# XmasTreeCard.net
KiCad netlist of a schematic drawn in EAGLE
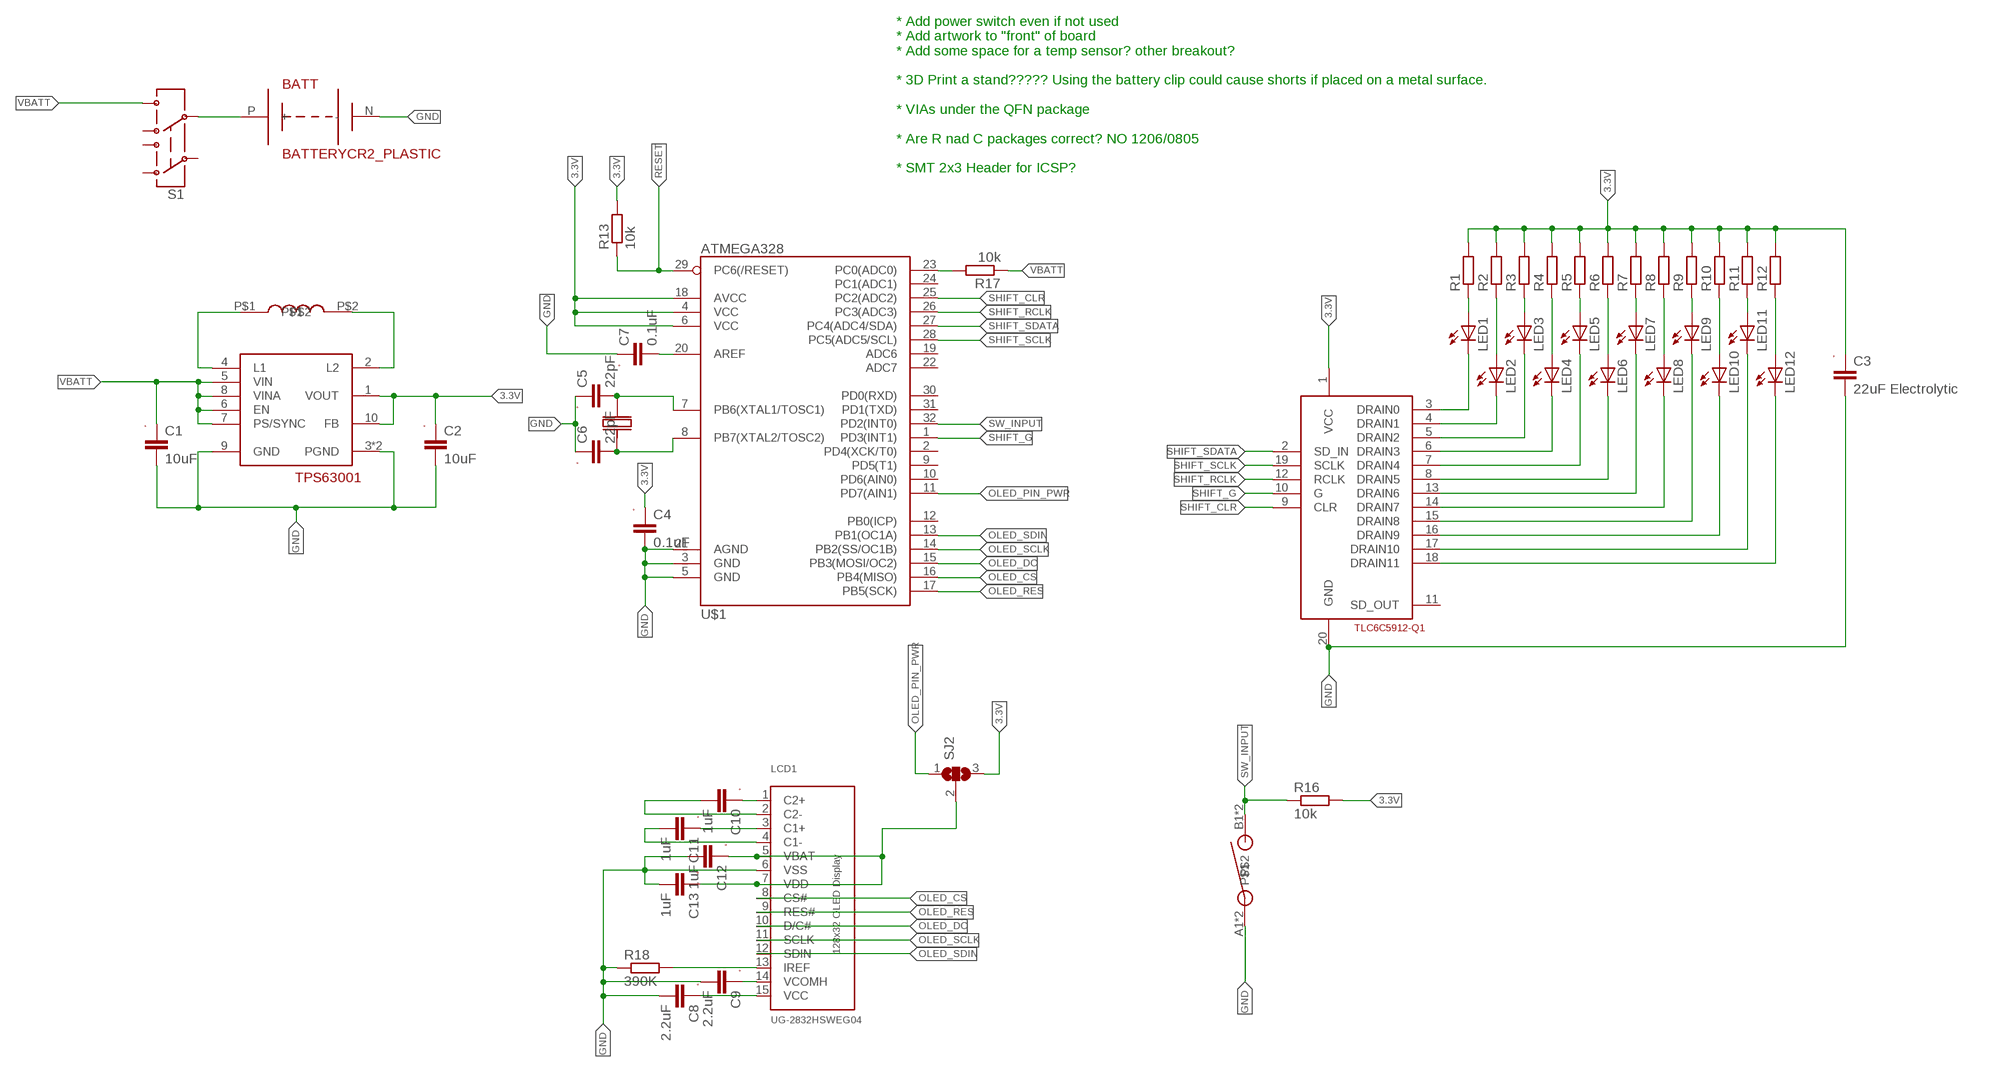
[diagram p0: schematic, sheet 1]

(export (version "E")
  (design (tool "Eeschema 10.0.6"))
  (components
    (comp (ref "BATT")
      (value "BATTERYCR2_PLASTIC")
      (footprint "eagle-import:BATT_SMD_CR2_PLASTIC")
      (libsource (lib "eagle-import") (part "BATTERYCR2_PLASTIC"))
    )
    (comp (ref "C1")
      (value "10uF")
      (footprint "eagle-import:C1206")
      (libsource (lib "eagle-import") (part "C-EUC1206"))
    )
    (comp (ref "C2")
      (value "10uF")
      (footprint "eagle-import:C1206")
      (libsource (lib "eagle-import") (part "C-EUC1206"))
    )
    (comp (ref "C3")
      (value "22uF Electrolytic")
      (footprint "eagle-import:CAP_2012-15")
      (libsource (lib "eagle-import") (part "C-EUAVX_TAJ_P"))
    )
    (comp (ref "C4")
      (value "0.1uF")
      (footprint "eagle-import:C0805K")
      (libsource (lib "eagle-import") (part "C-EUC0805K"))
    )
    (comp (ref "C5")
      (value "22pF")
      (footprint "eagle-import:C0805K")
      (libsource (lib "eagle-import") (part "C-EUC0805K"))
    )
    (comp (ref "C6")
      (value "22pF")
      (footprint "eagle-import:C0805K")
      (libsource (lib "eagle-import") (part "C-EUC0805K"))
    )
    (comp (ref "C7")
      (value "0.1uF")
      (footprint "eagle-import:C0805K")
      (libsource (lib "eagle-import") (part "C-EUC0805K"))
    )
    (comp (ref "C8")
      (value "2.2uF")
      (footprint "eagle-import:C1206")
      (libsource (lib "eagle-import") (part "C-EUC1206"))
    )
    (comp (ref "C9")
      (value "2.2uF")
      (footprint "eagle-import:C1206")
      (libsource (lib "eagle-import") (part "C-EUC1206"))
    )
    (comp (ref "C10")
      (value "1uF")
      (footprint "eagle-import:C1206")
      (libsource (lib "eagle-import") (part "C-EUC1206"))
    )
    (comp (ref "C11")
      (value "1uF")
      (footprint "eagle-import:C1206")
      (libsource (lib "eagle-import") (part "C-EUC1206"))
    )
    (comp (ref "C12")
      (value "1uF")
      (footprint "eagle-import:C1206")
      (libsource (lib "eagle-import") (part "C-EUC1206"))
    )
    (comp (ref "C13")
      (value "1uF")
      (footprint "eagle-import:C1206")
      (libsource (lib "eagle-import") (part "C-EUC1206"))
    )
    (comp (ref "LCD1")
      (value "UG-2832HSWEG04")
      (footprint "eagle-import:UG-283HSWEG04_FOLDAROUND")
      (libsource (lib "eagle-import") (part "OLED_UG-2832HSWEG04FOLDAROUND"))
    )
    (comp (ref "LED1")
      (value "LEDCHIPLED_0805")
      (footprint "eagle-import:CHIPLED_0805")
      (libsource (lib "eagle-import") (part "LEDCHIPLED_0805"))
    )
    (comp (ref "LED2")
      (value "LEDCHIPLED_0805")
      (footprint "eagle-import:CHIPLED_0805")
      (libsource (lib "eagle-import") (part "LEDCHIPLED_0805"))
    )
    (comp (ref "LED3")
      (value "LEDCHIPLED_0805")
      (footprint "eagle-import:CHIPLED_0805")
      (libsource (lib "eagle-import") (part "LEDCHIPLED_0805"))
    )
    (comp (ref "LED4")
      (value "LEDCHIPLED_0805")
      (footprint "eagle-import:CHIPLED_0805")
      (libsource (lib "eagle-import") (part "LEDCHIPLED_0805"))
    )
    (comp (ref "LED5")
      (value "LEDCHIPLED_0805")
      (footprint "eagle-import:CHIPLED_0805")
      (libsource (lib "eagle-import") (part "LEDCHIPLED_0805"))
    )
    (comp (ref "LED6")
      (value "LEDCHIPLED_0805")
      (footprint "eagle-import:CHIPLED_0805")
      (libsource (lib "eagle-import") (part "LEDCHIPLED_0805"))
    )
    (comp (ref "LED7")
      (value "LEDCHIPLED_0805")
      (footprint "eagle-import:CHIPLED_0805")
      (libsource (lib "eagle-import") (part "LEDCHIPLED_0805"))
    )
    (comp (ref "LED8")
      (value "LEDCHIPLED_0805")
      (footprint "eagle-import:CHIPLED_0805")
      (libsource (lib "eagle-import") (part "LEDCHIPLED_0805"))
    )
    (comp (ref "LED9")
      (value "LEDCHIPLED_0805")
      (footprint "eagle-import:CHIPLED_0805")
      (libsource (lib "eagle-import") (part "LEDCHIPLED_0805"))
    )
    (comp (ref "LED10")
      (value "LEDCHIPLED_0805")
      (footprint "eagle-import:CHIPLED_0805")
      (libsource (lib "eagle-import") (part "LEDCHIPLED_0805"))
    )
    (comp (ref "LED11")
      (value "LEDCHIPLED_0805")
      (footprint "eagle-import:CHIPLED_0805")
      (libsource (lib "eagle-import") (part "LEDCHIPLED_0805"))
    )
    (comp (ref "LED12")
      (value "LEDCHIPLED_0805")
      (footprint "eagle-import:CHIPLED_0805")
      (libsource (lib "eagle-import") (part "LEDCHIPLED_0805"))
    )
    (comp (ref "R1")
      (value "R-EUR0805")
      (footprint "eagle-import:R0805")
      (libsource (lib "eagle-import") (part "R-EUR0805"))
    )
    (comp (ref "R2")
      (value "R-EUR0805")
      (footprint "eagle-import:R0805")
      (libsource (lib "eagle-import") (part "R-EUR0805"))
    )
    (comp (ref "R3")
      (value "R-EUR0805")
      (footprint "eagle-import:R0805")
      (libsource (lib "eagle-import") (part "R-EUR0805"))
    )
    (comp (ref "R4")
      (value "R-EUR0805")
      (footprint "eagle-import:R0805")
      (libsource (lib "eagle-import") (part "R-EUR0805"))
    )
    (comp (ref "R5")
      (value "R-EUR0805")
      (footprint "eagle-import:R0805")
      (libsource (lib "eagle-import") (part "R-EUR0805"))
    )
    (comp (ref "R6")
      (value "R-EUR0805")
      (footprint "eagle-import:R0805")
      (libsource (lib "eagle-import") (part "R-EUR0805"))
    )
    (comp (ref "R7")
      (value "R-EUR0805")
      (footprint "eagle-import:R0805")
      (libsource (lib "eagle-import") (part "R-EUR0805"))
    )
    (comp (ref "R8")
      (value "R-EUR0805")
      (footprint "eagle-import:R0805")
      (libsource (lib "eagle-import") (part "R-EUR0805"))
    )
    (comp (ref "R9")
      (value "R-EUR0805")
      (footprint "eagle-import:R0805")
      (libsource (lib "eagle-import") (part "R-EUR0805"))
    )
    (comp (ref "R10")
      (value "R-EUR0805")
      (footprint "eagle-import:R0805")
      (libsource (lib "eagle-import") (part "R-EUR0805"))
    )
    (comp (ref "R11")
      (value "R-EUR0805")
      (footprint "eagle-import:R0805")
      (libsource (lib "eagle-import") (part "R-EUR0805"))
    )
    (comp (ref "R12")
      (value "R-EUR0805")
      (footprint "eagle-import:R0805")
      (libsource (lib "eagle-import") (part "R-EUR0805"))
    )
    (comp (ref "R13")
      (value "10k")
      (footprint "eagle-import:R0805")
      (libsource (lib "eagle-import") (part "R-EUR0805"))
    )
    (comp (ref "R16")
      (value "10k")
      (footprint "eagle-import:R0805")
      (libsource (lib "eagle-import") (part "R-EUR0805"))
    )
    (comp (ref "R17")
      (value "10k")
      (footprint "eagle-import:R0805")
      (libsource (lib "eagle-import") (part "R-EUR0805"))
    )
    (comp (ref "R18")
      (value "390K")
      (footprint "eagle-import:R0805")
      (libsource (lib "eagle-import") (part "R-EUR0805"))
    )
    (comp (ref "S1")
      (value "SWITCH-DPDTMMS228")
      (footprint "eagle-import:MMS_228_T")
      (libsource (lib "eagle-import") (part "SWITCH-DPDTMMS228"))
    )
    (comp (ref "SJ2")
      (value "SJ2W")
      (footprint "eagle-import:SJ_2")
      (libsource (lib "eagle-import") (part "SJ2W"))
    )
    (comp (ref "SW1")
      (value "SWITCH_SPST6X6TACTILE")
      (footprint "eagle-import:SWITCH_SPST_6X6_TACTILE")
      (libsource (lib "eagle-import") (part "SWITCH_SPST6X6TACTILE"))
    )
    (comp (ref "U$1")
      (value "ATMEGA328")
      (footprint "eagle-import:TQFP32-08")
      (libsource (lib "eagle-import") (part "ATMEGA328_SMT"))
    )
    (comp (ref "U$2")
      (value "COILCRAFT_LPS4012")
      (footprint "eagle-import:COILCRAFT_LPS4012")
      (libsource (lib "eagle-import") (part "COILCRAFT_LPS4012"))
    )
    (comp (ref "U$3")
      (value "TPS63001DRC")
      (footprint "eagle-import:QFN10_3X3MM")
      (libsource (lib "eagle-import") (part "TPS63001DRC"))
    )
    (comp (ref "U$4")
      (value "TLC6C5912-Q1")
      (footprint "eagle-import:TSSOP-20")
      (libsource (lib "eagle-import") (part "TLC6C5912-Q1"))
    )
    (comp (ref "U$5")
      (value "CRYSTAL_ABM03")
      (footprint "eagle-import:ABM_CRYSTAL")
      (libsource (lib "eagle-import") (part "CRYSTAL_ABM03"))
    )
  )
  (nets
    (net (code "1") (name "3.3V") (class "Default")
      (node (ref "C2") (pin "1") (pinfunction "1_1") (pintype "passive"))
      (node (ref "C3") (pin "P") (pinfunction "1_P") (pintype "passive"))
      (node (ref "C4") (pin "1") (pinfunction "1_1") (pintype "passive"))
      (node (ref "R1") (pin "2") (pinfunction "2_2") (pintype "passive"))
      (node (ref "R10") (pin "2") (pinfunction "2_2") (pintype "passive"))
      (node (ref "R11") (pin "2") (pinfunction "2_2") (pintype "passive"))
      (node (ref "R12") (pin "2") (pinfunction "2_2") (pintype "passive"))
      (node (ref "R13") (pin "2") (pinfunction "2_2") (pintype "passive"))
      (node (ref "R16") (pin "2") (pinfunction "2_2") (pintype "passive"))
      (node (ref "R2") (pin "2") (pinfunction "2_2") (pintype "passive"))
      (node (ref "R3") (pin "2") (pinfunction "2_2") (pintype "passive"))
      (node (ref "R4") (pin "2") (pinfunction "2_2") (pintype "passive"))
      (node (ref "R5") (pin "2") (pinfunction "2_2") (pintype "passive"))
      (node (ref "R6") (pin "2") (pinfunction "2_2") (pintype "passive"))
      (node (ref "R7") (pin "2") (pinfunction "2_2") (pintype "passive"))
      (node (ref "R8") (pin "2") (pinfunction "2_2") (pintype "passive"))
      (node (ref "R9") (pin "2") (pinfunction "2_2") (pintype "passive"))
      (node (ref "SJ2") (pin "3") (pinfunction "3_3") (pintype "passive"))
      (node (ref "U$1") (pin "18") (pinfunction "AVCC_18") (pintype "bidirectional"))
      (node (ref "U$1") (pin "4") (pinfunction "VCC_4") (pintype "bidirectional"))
      (node (ref "U$1") (pin "6") (pinfunction "VCC_6") (pintype "bidirectional"))
      (node (ref "U$3") (pin "1") (pinfunction "VOUT_1") (pintype "bidirectional"))
      (node (ref "U$3") (pin "10") (pinfunction "FB_10") (pintype "bidirectional"))
      (node (ref "U$4") (pin "1") (pinfunction "VCC_1") (pintype "bidirectional"))
    )
    (net (code "2") (name "GND") (class "Default")
      (node (ref "BATT") (pin "N") (pinfunction "-_N") (pintype "bidirectional"))
      (node (ref "C1") (pin "2") (pinfunction "2_2") (pintype "passive"))
      (node (ref "C12") (pin "2") (pinfunction "2_2") (pintype "passive"))
      (node (ref "C13") (pin "2") (pinfunction "2_2") (pintype "passive"))
      (node (ref "C2") (pin "2") (pinfunction "2_2") (pintype "passive"))
      (node (ref "C3") (pin "N") (pinfunction "2_N") (pintype "passive"))
      (node (ref "C4") (pin "2") (pinfunction "2_2") (pintype "passive"))
      (node (ref "C5") (pin "1") (pinfunction "1_1") (pintype "passive"))
      (node (ref "C6") (pin "1") (pinfunction "1_1") (pintype "passive"))
      (node (ref "C7") (pin "1") (pinfunction "1_1") (pintype "passive"))
      (node (ref "C8") (pin "2") (pinfunction "2_2") (pintype "passive"))
      (node (ref "C9") (pin "2") (pinfunction "2_2") (pintype "passive"))
      (node (ref "LCD1") (pin "6") (pinfunction "VSS_6") (pintype "bidirectional"))
      (node (ref "R18") (pin "1") (pinfunction "1_1") (pintype "passive"))
      (node (ref "SW1") (pin "A1") (pinfunction "P$1_A1") (pintype "bidirectional"))
      (node (ref "SW1") (pin "A2") (pinfunction "P$1_A2") (pintype "bidirectional"))
      (node (ref "U$1") (pin "21") (pinfunction "AGND_21") (pintype "bidirectional"))
      (node (ref "U$1") (pin "3") (pinfunction "GND_3") (pintype "bidirectional"))
      (node (ref "U$1") (pin "5") (pinfunction "GND_5") (pintype "bidirectional"))
      (node (ref "U$3") (pin "11") (pinfunction "PGND_11") (pintype "bidirectional"))
      (node (ref "U$3") (pin "3") (pinfunction "PGND_3") (pintype "bidirectional"))
      (node (ref "U$3") (pin "9") (pinfunction "GND_9") (pintype "bidirectional"))
      (node (ref "U$4") (pin "20") (pinfunction "GND_20") (pintype "bidirectional"))
    )
    (net (code "3") (name "Net-(BATT-+)") (class "Default")
      (node (ref "BATT") (pin "P") (pinfunction "+_P") (pintype "bidirectional"))
      (node (ref "S1") (pin "6") (pinfunction "5_6") (pintype "bidirectional"))
    )
    (net (code "4") (name "Net-(LCD1-C1+)") (class "Default")
      (node (ref "C11") (pin "1") (pinfunction "1_1") (pintype "passive"))
      (node (ref "LCD1") (pin "3") (pinfunction "C1+_3") (pintype "bidirectional"))
    )
    (net (code "5") (name "Net-(LCD1-C1-)") (class "Default")
      (node (ref "C11") (pin "2") (pinfunction "2_2") (pintype "passive"))
      (node (ref "LCD1") (pin "4") (pinfunction "C1-_4") (pintype "bidirectional"))
    )
    (net (code "6") (name "Net-(LCD1-C2+)") (class "Default")
      (node (ref "C10") (pin "1") (pinfunction "1_1") (pintype "passive"))
      (node (ref "LCD1") (pin "1") (pinfunction "C2+_1") (pintype "bidirectional"))
    )
    (net (code "7") (name "Net-(LCD1-C2-)") (class "Default")
      (node (ref "C10") (pin "2") (pinfunction "2_2") (pintype "passive"))
      (node (ref "LCD1") (pin "2") (pinfunction "C2-_2") (pintype "bidirectional"))
    )
    (net (code "8") (name "Net-(LCD1-IREF)") (class "Default")
      (node (ref "LCD1") (pin "13") (pinfunction "IREF_13") (pintype "bidirectional"))
      (node (ref "R18") (pin "2") (pinfunction "2_2") (pintype "passive"))
    )
    (net (code "9") (name "Net-(LCD1-VBAT)") (class "Default")
      (node (ref "C12") (pin "1") (pinfunction "1_1") (pintype "passive"))
      (node (ref "C13") (pin "1") (pinfunction "1_1") (pintype "passive"))
      (node (ref "LCD1") (pin "5") (pinfunction "VBAT_5") (pintype "bidirectional"))
      (node (ref "LCD1") (pin "7") (pinfunction "VDD_7") (pintype "bidirectional"))
      (node (ref "SJ2") (pin "2") (pinfunction "2_2") (pintype "passive"))
    )
    (net (code "10") (name "Net-(LCD1-VCC)") (class "Default")
      (node (ref "C8") (pin "1") (pinfunction "1_1") (pintype "passive"))
      (node (ref "LCD1") (pin "15") (pinfunction "VCC_15") (pintype "bidirectional"))
    )
    (net (code "11") (name "Net-(LCD1-VCOMH)") (class "Default")
      (node (ref "C9") (pin "1") (pinfunction "1_1") (pintype "passive"))
      (node (ref "LCD1") (pin "14") (pinfunction "VCOMH_14") (pintype "bidirectional"))
    )
    (net (code "12") (name "Net-(LED1-PadA)") (class "Default")
      (node (ref "LED1") (pin "A") (pinfunction "A_A") (pintype "passive"))
      (node (ref "R1") (pin "1") (pinfunction "1_1") (pintype "passive"))
    )
    (net (code "13") (name "Net-(LED2-PadA)") (class "Default")
      (node (ref "LED2") (pin "A") (pinfunction "A_A") (pintype "passive"))
      (node (ref "R2") (pin "1") (pinfunction "1_1") (pintype "passive"))
    )
    (net (code "14") (name "Net-(LED3-PadA)") (class "Default")
      (node (ref "LED3") (pin "A") (pinfunction "A_A") (pintype "passive"))
      (node (ref "R3") (pin "1") (pinfunction "1_1") (pintype "passive"))
    )
    (net (code "15") (name "Net-(LED4-PadA)") (class "Default")
      (node (ref "LED4") (pin "A") (pinfunction "A_A") (pintype "passive"))
      (node (ref "R4") (pin "1") (pinfunction "1_1") (pintype "passive"))
    )
    (net (code "16") (name "Net-(LED5-PadA)") (class "Default")
      (node (ref "LED5") (pin "A") (pinfunction "A_A") (pintype "passive"))
      (node (ref "R5") (pin "1") (pinfunction "1_1") (pintype "passive"))
    )
    (net (code "17") (name "Net-(LED6-PadA)") (class "Default")
      (node (ref "LED6") (pin "A") (pinfunction "A_A") (pintype "passive"))
      (node (ref "R6") (pin "1") (pinfunction "1_1") (pintype "passive"))
    )
    (net (code "18") (name "Net-(LED7-PadA)") (class "Default")
      (node (ref "LED7") (pin "A") (pinfunction "A_A") (pintype "passive"))
      (node (ref "R7") (pin "1") (pinfunction "1_1") (pintype "passive"))
    )
    (net (code "19") (name "Net-(LED8-PadA)") (class "Default")
      (node (ref "LED8") (pin "A") (pinfunction "A_A") (pintype "passive"))
      (node (ref "R8") (pin "1") (pinfunction "1_1") (pintype "passive"))
    )
    (net (code "20") (name "Net-(LED9-PadA)") (class "Default")
      (node (ref "LED9") (pin "A") (pinfunction "A_A") (pintype "passive"))
      (node (ref "R9") (pin "1") (pinfunction "1_1") (pintype "passive"))
    )
    (net (code "21") (name "Net-(LED10-PadA)") (class "Default")
      (node (ref "LED10") (pin "A") (pinfunction "A_A") (pintype "passive"))
      (node (ref "R10") (pin "1") (pinfunction "1_1") (pintype "passive"))
    )
    (net (code "22") (name "Net-(LED11-PadA)") (class "Default")
      (node (ref "LED11") (pin "A") (pinfunction "A_A") (pintype "passive"))
      (node (ref "R11") (pin "1") (pinfunction "1_1") (pintype "passive"))
    )
    (net (code "23") (name "Net-(LED12-PadA)") (class "Default")
      (node (ref "LED12") (pin "A") (pinfunction "A_A") (pintype "passive"))
      (node (ref "R12") (pin "1") (pinfunction "1_1") (pintype "passive"))
    )
    (net (code "24") (name "Net-(U$1-AREF)") (class "Default")
      (node (ref "C7") (pin "2") (pinfunction "2_2") (pintype "passive"))
      (node (ref "U$1") (pin "20") (pinfunction "AREF_20") (pintype "bidirectional"))
    )
    (net (code "25") (name "Net-(U$1-PB6(XTAL1{slash}TOSC1))") (class "Default")
      (node (ref "C5") (pin "2") (pinfunction "2_2") (pintype "passive"))
      (node (ref "U$1") (pin "7") (pinfunction "PB6(XTAL1/TOSC1)_7") (pintype "bidirectional"))
      (node (ref "U$5") (pin "2") (pinfunction "2_2") (pintype "bidirectional"))
    )
    (net (code "26") (name "Net-(U$1-PB7(XTAL2{slash}TOSC2))") (class "Default")
      (node (ref "C6") (pin "2") (pinfunction "2_2") (pintype "passive"))
      (node (ref "U$1") (pin "8") (pinfunction "PB7(XTAL2/TOSC2)_8") (pintype "bidirectional"))
      (node (ref "U$5") (pin "1") (pinfunction "1_1") (pintype "bidirectional"))
    )
    (net (code "27") (name "Net-(U$1-PC0(ADC0))") (class "Default")
      (node (ref "R17") (pin "2") (pinfunction "2_2") (pintype "passive"))
      (node (ref "U$1") (pin "23") (pinfunction "PC0(ADC0)_23") (pintype "bidirectional"))
    )
    (net (code "28") (name "Net-(U$3-L1)") (class "Default")
      (node (ref "U$2") (pin "P$1") (pinfunction "P$1_P$1") (pintype "bidirectional"))
      (node (ref "U$3") (pin "4") (pinfunction "L1_4") (pintype "bidirectional"))
    )
    (net (code "29") (name "Net-(U$3-L2)") (class "Default")
      (node (ref "U$2") (pin "P$2") (pinfunction "P$2_P$2") (pintype "bidirectional"))
      (node (ref "U$3") (pin "2") (pinfunction "L2_2") (pintype "bidirectional"))
    )
    (net (code "30") (name "Net-(U$4-DRAIN0)") (class "Default")
      (node (ref "LED1") (pin "C") (pinfunction "C_C") (pintype "passive"))
      (node (ref "U$4") (pin "3") (pinfunction "DRAIN0_3") (pintype "bidirectional"))
    )
    (net (code "31") (name "Net-(U$4-DRAIN1)") (class "Default")
      (node (ref "LED2") (pin "C") (pinfunction "C_C") (pintype "passive"))
      (node (ref "U$4") (pin "4") (pinfunction "DRAIN1_4") (pintype "bidirectional"))
    )
    (net (code "32") (name "Net-(U$4-DRAIN2)") (class "Default")
      (node (ref "LED3") (pin "C") (pinfunction "C_C") (pintype "passive"))
      (node (ref "U$4") (pin "5") (pinfunction "DRAIN2_5") (pintype "bidirectional"))
    )
    (net (code "33") (name "Net-(U$4-DRAIN3)") (class "Default")
      (node (ref "LED4") (pin "C") (pinfunction "C_C") (pintype "passive"))
      (node (ref "U$4") (pin "6") (pinfunction "DRAIN3_6") (pintype "bidirectional"))
    )
    (net (code "34") (name "Net-(U$4-DRAIN4)") (class "Default")
      (node (ref "LED5") (pin "C") (pinfunction "C_C") (pintype "passive"))
      (node (ref "U$4") (pin "7") (pinfunction "DRAIN4_7") (pintype "bidirectional"))
    )
    (net (code "35") (name "Net-(U$4-DRAIN5)") (class "Default")
      (node (ref "LED6") (pin "C") (pinfunction "C_C") (pintype "passive"))
      (node (ref "U$4") (pin "8") (pinfunction "DRAIN5_8") (pintype "bidirectional"))
    )
    (net (code "36") (name "Net-(U$4-DRAIN6)") (class "Default")
      (node (ref "LED7") (pin "C") (pinfunction "C_C") (pintype "passive"))
      (node (ref "U$4") (pin "13") (pinfunction "DRAIN6_13") (pintype "bidirectional"))
    )
    (net (code "37") (name "Net-(U$4-DRAIN7)") (class "Default")
      (node (ref "LED8") (pin "C") (pinfunction "C_C") (pintype "passive"))
      (node (ref "U$4") (pin "14") (pinfunction "DRAIN7_14") (pintype "bidirectional"))
    )
    (net (code "38") (name "Net-(U$4-DRAIN8)") (class "Default")
      (node (ref "LED9") (pin "C") (pinfunction "C_C") (pintype "passive"))
      (node (ref "U$4") (pin "15") (pinfunction "DRAIN8_15") (pintype "bidirectional"))
    )
    (net (code "39") (name "Net-(U$4-DRAIN9)") (class "Default")
      (node (ref "LED10") (pin "C") (pinfunction "C_C") (pintype "passive"))
      (node (ref "U$4") (pin "16") (pinfunction "DRAIN9_16") (pintype "bidirectional"))
    )
    (net (code "40") (name "Net-(U$4-DRAIN10)") (class "Default")
      (node (ref "LED11") (pin "C") (pinfunction "C_C") (pintype "passive"))
      (node (ref "U$4") (pin "17") (pinfunction "DRAIN10_17") (pintype "bidirectional"))
    )
    (net (code "41") (name "Net-(U$4-DRAIN11)") (class "Default")
      (node (ref "LED12") (pin "C") (pinfunction "C_C") (pintype "passive"))
      (node (ref "U$4") (pin "18") (pinfunction "DRAIN11_18") (pintype "bidirectional"))
    )
    (net (code "42") (name "OLED_CS") (class "Default")
      (node (ref "LCD1") (pin "8") (pinfunction "CS#_8") (pintype "bidirectional"))
      (node (ref "U$1") (pin "16") (pinfunction "PB4(MISO)_16") (pintype "bidirectional"))
    )
    (net (code "43") (name "OLED_DC") (class "Default")
      (node (ref "LCD1") (pin "10") (pinfunction "D/C#_10") (pintype "bidirectional"))
      (node (ref "U$1") (pin "15") (pinfunction "PB3(MOSI/OC2)_15") (pintype "bidirectional"))
    )
    (net (code "44") (name "OLED_PIN_PWR") (class "Default")
      (node (ref "SJ2") (pin "1") (pinfunction "1_1") (pintype "passive"))
      (node (ref "U$1") (pin "11") (pinfunction "PD7(AIN1)_11") (pintype "bidirectional"))
    )
    (net (code "45") (name "OLED_RES") (class "Default")
      (node (ref "LCD1") (pin "9") (pinfunction "RES#_9") (pintype "bidirectional"))
      (node (ref "U$1") (pin "17") (pinfunction "PB5(SCK)_17") (pintype "bidirectional"))
    )
    (net (code "46") (name "OLED_SCLK") (class "Default")
      (node (ref "LCD1") (pin "11") (pinfunction "SCLK_11") (pintype "bidirectional"))
      (node (ref "U$1") (pin "14") (pinfunction "PB2(SS/OC1B)_14") (pintype "bidirectional"))
    )
    (net (code "47") (name "OLED_SDIN") (class "Default")
      (node (ref "LCD1") (pin "12") (pinfunction "SDIN_12") (pintype "bidirectional"))
      (node (ref "U$1") (pin "13") (pinfunction "PB1(OC1A)_13") (pintype "bidirectional"))
    )
    (net (code "48") (name "RESET") (class "Default")
      (node (ref "R13") (pin "1") (pinfunction "1_1") (pintype "passive"))
      (node (ref "U$1") (pin "29") (pinfunction "PC6(/RESET)_29") (pintype "bidirectional"))
    )
    (net (code "49") (name "SHIFT_CLR") (class "Default")
      (node (ref "U$1") (pin "25") (pinfunction "PC2(ADC2)_25") (pintype "bidirectional"))
      (node (ref "U$4") (pin "9") (pinfunction "CLR_9") (pintype "bidirectional"))
    )
    (net (code "50") (name "SHIFT_G") (class "Default")
      (node (ref "U$1") (pin "1") (pinfunction "PD3(INT1)_1") (pintype "bidirectional"))
      (node (ref "U$4") (pin "10") (pinfunction "G_10") (pintype "bidirectional"))
    )
    (net (code "51") (name "SHIFT_RCLK") (class "Default")
      (node (ref "U$1") (pin "26") (pinfunction "PC3(ADC3)_26") (pintype "bidirectional"))
      (node (ref "U$4") (pin "12") (pinfunction "RCLK_12") (pintype "bidirectional"))
    )
    (net (code "52") (name "SHIFT_SCLK") (class "Default")
      (node (ref "U$1") (pin "28") (pinfunction "PC5(ADC5/SCL)_28") (pintype "bidirectional"))
      (node (ref "U$4") (pin "19") (pinfunction "SCLK_19") (pintype "bidirectional"))
    )
    (net (code "53") (name "SHIFT_SDATA") (class "Default")
      (node (ref "U$1") (pin "27") (pinfunction "PC4(ADC4/SDA)_27") (pintype "bidirectional"))
      (node (ref "U$4") (pin "2") (pinfunction "SD_IN_2") (pintype "bidirectional"))
    )
    (net (code "54") (name "SW_INPUT") (class "Default")
      (node (ref "R16") (pin "1") (pinfunction "1_1") (pintype "passive"))
      (node (ref "SW1") (pin "B1") (pinfunction "P$2_B1") (pintype "bidirectional"))
      (node (ref "SW1") (pin "B2") (pinfunction "P$2_B2") (pintype "bidirectional"))
      (node (ref "U$1") (pin "32") (pinfunction "PD2(INT0)_32") (pintype "bidirectional"))
    )
    (net (code "55") (name "VBATT") (class "Default")
      (node (ref "C1") (pin "1") (pinfunction "1_1") (pintype "passive"))
      (node (ref "R17") (pin "1") (pinfunction "1_1") (pintype "passive"))
      (node (ref "S1") (pin "7") (pinfunction "6_7") (pintype "bidirectional"))
      (node (ref "U$3") (pin "5") (pinfunction "VIN_5") (pintype "bidirectional"))
      (node (ref "U$3") (pin "6") (pinfunction "EN_6") (pintype "bidirectional"))
      (node (ref "U$3") (pin "7") (pinfunction "PS/SYNC_7") (pintype "bidirectional"))
      (node (ref "U$3") (pin "8") (pinfunction "VINA_8") (pintype "bidirectional"))
    )
    (net (code "56") (name "unconnected-(S1-4-Pad5)") (class "Default")
      (node (ref "S1") (pin "5") (pinfunction "4_5") (pintype "bidirectional"))
    )
    (net (code "57") (name "unconnected-(S1-Pad1)") (class "Default")
      (node (ref "S1") (pin "1") (pinfunction "1_1") (pintype "bidirectional"))
    )
    (net (code "58") (name "unconnected-(S1-Pad2)") (class "Default")
      (node (ref "S1") (pin "2") (pinfunction "2_2") (pintype "bidirectional"))
    )
    (net (code "59") (name "unconnected-(S1-Pad3)") (class "Default")
      (node (ref "S1") (pin "3") (pinfunction "3_3") (pintype "bidirectional"))
    )
    (net (code "60") (name "unconnected-(U$1-ADC6-Pad19)") (class "Default")
      (node (ref "U$1") (pin "19") (pinfunction "ADC6_19") (pintype "bidirectional"))
    )
    (net (code "61") (name "unconnected-(U$1-ADC7-Pad22)") (class "Default")
      (node (ref "U$1") (pin "22") (pinfunction "ADC7_22") (pintype "bidirectional"))
    )
    (net (code "62") (name "unconnected-(U$1-PB0(ICP)-Pad12)") (class "Default")
      (node (ref "U$1") (pin "12") (pinfunction "PB0(ICP)_12") (pintype "bidirectional"))
    )
    (net (code "63") (name "unconnected-(U$1-PC1(ADC1)-Pad24)") (class "Default")
      (node (ref "U$1") (pin "24") (pinfunction "PC1(ADC1)_24") (pintype "bidirectional"))
    )
    (net (code "64") (name "unconnected-(U$1-PD0(RXD)-Pad30)") (class "Default")
      (node (ref "U$1") (pin "30") (pinfunction "PD0(RXD)_30") (pintype "bidirectional"))
    )
    (net (code "65") (name "unconnected-(U$1-PD1(TXD)-Pad31)") (class "Default")
      (node (ref "U$1") (pin "31") (pinfunction "PD1(TXD)_31") (pintype "bidirectional"))
    )
    (net (code "66") (name "unconnected-(U$1-PD4(XCK{slash}T0)-Pad2)") (class "Default")
      (node (ref "U$1") (pin "2") (pinfunction "PD4(XCK/T0)_2") (pintype "bidirectional"))
    )
    (net (code "67") (name "unconnected-(U$1-PD5(T1)-Pad9)") (class "Default")
      (node (ref "U$1") (pin "9") (pinfunction "PD5(T1)_9") (pintype "bidirectional"))
    )
    (net (code "68") (name "unconnected-(U$1-PD6(AIN0)-Pad10)") (class "Default")
      (node (ref "U$1") (pin "10") (pinfunction "PD6(AIN0)_10") (pintype "bidirectional"))
    )
    (net (code "69") (name "unconnected-(U$4-SD_OUT-Pad11)") (class "Default")
      (node (ref "U$4") (pin "11") (pinfunction "SD_OUT_11") (pintype "bidirectional"))
    )
  )
)
